# FMC_connector.net
KiCad netlist of a schematic drawn in Altium Designer
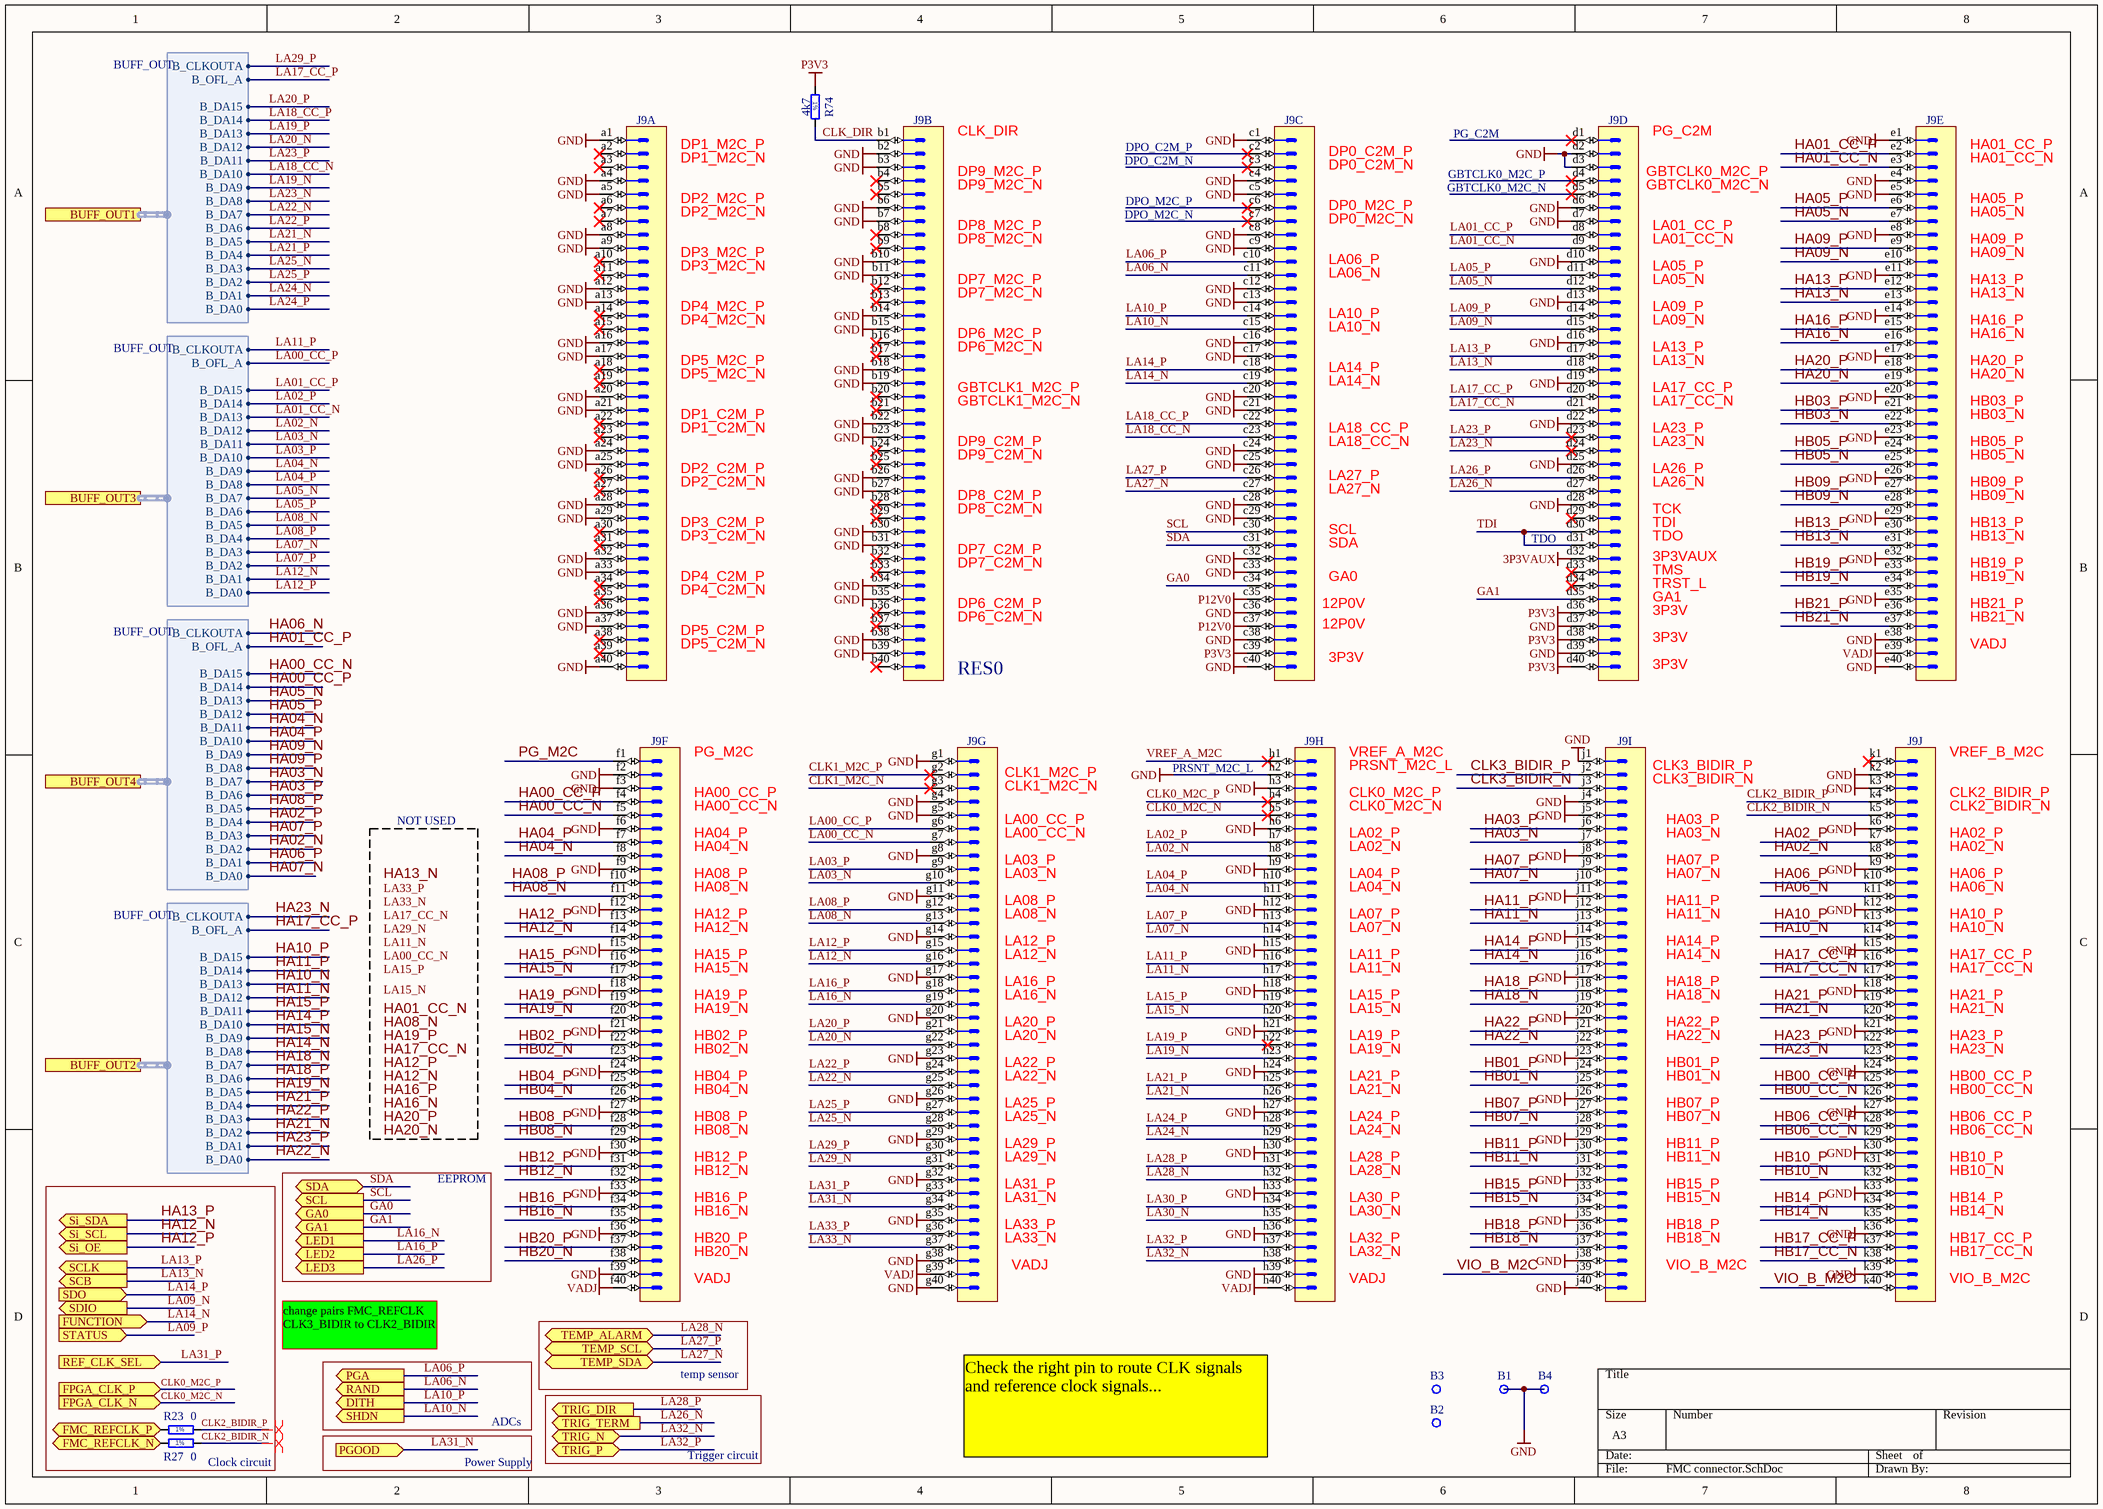
[diagram p0: FMC connector.SchDoc]

(export (version "E")
  (design (tool "Eeschema 10.0.6"))
  (components
    (comp (ref "B1")
      (value "Plated Hole")
      (footprint "MTG300_600")
      (description "Single Terminal Socket")
      (fields (field (name "PART NUMBER") "PLATED_HOLE3.0_PAD6.0") (field (name "AUTHOR") "CERN DEM JLC"))
      (libsource (lib "Eletro-mechanical") (part "Single Terminal Socket"))
    )
    (comp (ref "B2")
      (value "Plated Hole")
      (footprint "MTG300_600")
      (description "Single Terminal Socket")
      (fields (field (name "PART NUMBER") "PLATED_HOLE3.0_PAD6.0") (field (name "AUTHOR") "CERN DEM JLC"))
      (libsource (lib "Eletro-mechanical") (part "Single Terminal Socket"))
    )
    (comp (ref "B3")
      (value "Plated Hole")
      (footprint "MTG300_600")
      (description "Single Terminal Socket")
      (fields (field (name "PART NUMBER") "PLATED_HOLE3.0_PAD6.0") (field (name "AUTHOR") "CERN DEM JLC"))
      (libsource (lib "Eletro-mechanical") (part "Single Terminal Socket"))
    )
    (comp (ref "B4")
      (value "Plated Hole")
      (footprint "MTG300_600")
      (description "Single Terminal Socket")
      (fields (field (name "PART NUMBER") "PLATED_HOLE3.0_PAD6.0") (field (name "AUTHOR") "CERN DEM JLC"))
      (libsource (lib "Eletro-mechanical") (part "Single Terminal Socket"))
    )
    (comp (ref "J9")
      (value "VITA 57")
      (footprint "SAMTEC_ASP-134488-01")
      (description "Connector VITA 57, 400 Male contacts in 10 row abcdefghj")
      (fields
        (field (name "PART NUMBER") "SAMTEC_ASP-134488-01")
        (field (name "MANUFACTURER") "SAMTEC")
        (field (name "AUTHOR") "CERN DEM JLC")
      )
      (libsource (lib "Connectors") (part "Connector VITA 57 400 Male (abcdefghjk)"))
    )
    (comp (ref "R23")
      (value "0")
      (footprint "RESC1005X40N")
      (description "Resistor - 1%")
      (fields
        (field (name "PART NUMBER") "R0402_0R_JUMPER")
        (field (name "MANUFACTURER") "GENERIC")
        (field (name "AUTHOR") "CERN DEM JLC")
      )
      (libsource (lib "Resistors") (part "Resistor - 1%"))
    )
    (comp (ref "R27")
      (value "0")
      (footprint "RESC1005X40N")
      (description "Resistor - 1%")
      (fields
        (field (name "PART NUMBER") "R0402_0R_JUMPER")
        (field (name "MANUFACTURER") "GENERIC")
        (field (name "AUTHOR") "CERN DEM JLC")
      )
      (libsource (lib "Resistors") (part "Resistor - 1%"))
    )
    (comp (ref "R74")
      (value "4k7")
      (footprint "RESC1608X55N")
      (description "Resistor - 1%")
      (fields
        (field (name "PART NUMBER") "R0603_4K7_1%_0.1W_100PPM")
        (field (name "POWER") "0.1W")
        (field (name "AUTHOR") "CERN DEM JLC")
      )
      (libsource (lib "Resistors") (part "Resistor - 1%"))
    )
  )
  (nets
    (net (code "2") (name "/CLK0_M2C_N") (class "Default")
      (node (ref "J9") (pin "h5") (pinfunction "h5_h5") (pintype "bidirectional+no_connect"))
    )
    (net (code "3") (name "/CLK0_M2C_P") (class "Default")
      (node (ref "J9") (pin "h4") (pinfunction "h4_h4") (pintype "bidirectional+no_connect"))
    )
    (net (code "4") (name "/CLK1_M2C_N") (class "Default")
      (node (ref "J9") (pin "g3") (pinfunction "g3_g3") (pintype "bidirectional+no_connect"))
    )
    (net (code "5") (name "/CLK1_M2C_P") (class "Default")
      (node (ref "J9") (pin "g2") (pinfunction "g2_g2") (pintype "bidirectional+no_connect"))
    )
    (net (code "6") (name "/CLK2_BIDIR_N") (class "Default")
      (node (ref "J9") (pin "k5") (pinfunction "k5_k5") (pintype "bidirectional"))
      (node (ref "R27") (pin "2") (pinfunction "2_2") (pintype "passive"))
    )
    (net (code "7") (name "/CLK2_BIDIR_P") (class "Default")
      (node (ref "J9") (pin "k4") (pinfunction "k4_k4") (pintype "bidirectional"))
      (node (ref "R23") (pin "2") (pinfunction "2_2") (pintype "passive"))
    )
    (net (code "8") (name "/CLK3_BIDIR_N") (class "Default")
      (node (ref "J9") (pin "j3") (pinfunction "j3_j3") (pintype "bidirectional"))
    )
    (net (code "9") (name "/CLK3_BIDIR_P") (class "Default")
      (node (ref "J9") (pin "j2") (pinfunction "j2_j2") (pintype "bidirectional"))
    )
    (net (code "10") (name "/CLK_DIR") (class "Default")
      (node (ref "J9") (pin "b1") (pinfunction "b1_b1") (pintype "bidirectional"))
      (node (ref "R74") (pin "2") (pinfunction "2_2") (pintype "passive"))
    )
    (net (code "11") (name "/FMC_REFCLK_N") (class "Default")
      (node (ref "R27") (pin "1") (pinfunction "1_1") (pintype "passive"))
    )
    (net (code "12") (name "/FMC_REFCLK_P") (class "Default")
      (node (ref "R23") (pin "1") (pinfunction "1_1") (pintype "passive"))
    )
    (net (code "13") (name "/GA0") (class "Default")
      (node (ref "J9") (pin "c34") (pinfunction "c34_c34") (pintype "bidirectional"))
    )
    (net (code "14") (name "/GA1") (class "Default")
      (node (ref "J9") (pin "d35") (pinfunction "d35_d35") (pintype "bidirectional"))
    )
    (net (code "15") (name "/HA00_CC_N") (class "Default")
      (node (ref "J9") (pin "f5") (pinfunction "f5_f5") (pintype "bidirectional"))
    )
    (net (code "16") (name "/HA00_CC_P") (class "Default")
      (node (ref "J9") (pin "f4") (pinfunction "f4_f4") (pintype "bidirectional"))
    )
    (net (code "17") (name "/HA01_CC_N") (class "Default")
      (node (ref "J9") (pin "e3") (pinfunction "e3_e3") (pintype "bidirectional"))
    )
    (net (code "18") (name "/HA01_CC_P") (class "Default")
      (node (ref "J9") (pin "e2") (pinfunction "e2_e2") (pintype "bidirectional"))
    )
    (net (code "19") (name "/HA02_N") (class "Default")
      (node (ref "J9") (pin "k8") (pinfunction "k8_k8") (pintype "bidirectional"))
    )
    (net (code "20") (name "/HA02_P") (class "Default")
      (node (ref "J9") (pin "k7") (pinfunction "k7_k7") (pintype "bidirectional"))
    )
    (net (code "21") (name "/HA03_N") (class "Default")
      (node (ref "J9") (pin "j7") (pinfunction "j7_j7") (pintype "bidirectional"))
    )
    (net (code "22") (name "/HA03_P") (class "Default")
      (node (ref "J9") (pin "j6") (pinfunction "j6_j6") (pintype "bidirectional"))
    )
    (net (code "23") (name "/HA04_N") (class "Default")
      (node (ref "J9") (pin "f8") (pinfunction "f8_f8") (pintype "bidirectional"))
    )
    (net (code "24") (name "/HA04_P") (class "Default")
      (node (ref "J9") (pin "f7") (pinfunction "f7_f7") (pintype "bidirectional"))
    )
    (net (code "25") (name "/HA05_N") (class "Default")
      (node (ref "J9") (pin "e7") (pinfunction "e7_e7") (pintype "bidirectional"))
    )
    (net (code "26") (name "/HA05_P") (class "Default")
      (node (ref "J9") (pin "e6") (pinfunction "e6_e6") (pintype "bidirectional"))
    )
    (net (code "27") (name "/HA06_N") (class "Default")
      (node (ref "J9") (pin "k11") (pinfunction "k11_k11") (pintype "bidirectional"))
    )
    (net (code "28") (name "/HA06_P") (class "Default")
      (node (ref "J9") (pin "k10") (pinfunction "k10_k10") (pintype "bidirectional"))
    )
    (net (code "29") (name "/HA07_N") (class "Default")
      (node (ref "J9") (pin "j10") (pinfunction "j10_j10") (pintype "bidirectional"))
    )
    (net (code "30") (name "/HA07_P") (class "Default")
      (node (ref "J9") (pin "j9") (pinfunction "j9_j9") (pintype "bidirectional"))
    )
    (net (code "31") (name "/HA08_N") (class "Default")
      (node (ref "J9") (pin "f11") (pinfunction "f11_f11") (pintype "bidirectional"))
    )
    (net (code "32") (name "/HA08_P") (class "Default")
      (node (ref "J9") (pin "f10") (pinfunction "f10_f10") (pintype "bidirectional"))
    )
    (net (code "33") (name "/HA09_N") (class "Default")
      (node (ref "J9") (pin "e10") (pinfunction "e10_e10") (pintype "bidirectional"))
    )
    (net (code "34") (name "/HA09_P") (class "Default")
      (node (ref "J9") (pin "e9") (pinfunction "e9_e9") (pintype "bidirectional"))
    )
    (net (code "35") (name "/HA10_N") (class "Default")
      (node (ref "J9") (pin "k14") (pinfunction "k14_k14") (pintype "bidirectional"))
    )
    (net (code "36") (name "/HA10_P") (class "Default")
      (node (ref "J9") (pin "k13") (pinfunction "k13_k13") (pintype "bidirectional"))
    )
    (net (code "37") (name "/HA11_N") (class "Default")
      (node (ref "J9") (pin "j13") (pinfunction "j13_j13") (pintype "bidirectional"))
    )
    (net (code "38") (name "/HA11_P") (class "Default")
      (node (ref "J9") (pin "j12") (pinfunction "j12_j12") (pintype "bidirectional"))
    )
    (net (code "39") (name "/HA12_N") (class "Default")
      (node (ref "J9") (pin "f14") (pinfunction "f14_f14") (pintype "bidirectional"))
    )
    (net (code "40") (name "/HA12_P") (class "Default")
      (node (ref "J9") (pin "f13") (pinfunction "f13_f13") (pintype "bidirectional"))
    )
    (net (code "41") (name "/HA13_N") (class "Default")
      (node (ref "J9") (pin "e13") (pinfunction "e13_e13") (pintype "bidirectional"))
    )
    (net (code "42") (name "/HA13_P") (class "Default")
      (node (ref "J9") (pin "e12") (pinfunction "e12_e12") (pintype "bidirectional"))
    )
    (net (code "43") (name "/HA14_N") (class "Default")
      (node (ref "J9") (pin "j16") (pinfunction "j16_j16") (pintype "bidirectional"))
    )
    (net (code "44") (name "/HA14_P") (class "Default")
      (node (ref "J9") (pin "j15") (pinfunction "j15_j15") (pintype "bidirectional"))
    )
    (net (code "45") (name "/HA15_N") (class "Default")
      (node (ref "J9") (pin "f17") (pinfunction "f17_f17") (pintype "bidirectional"))
    )
    (net (code "46") (name "/HA15_P") (class "Default")
      (node (ref "J9") (pin "f16") (pinfunction "f16_f16") (pintype "bidirectional"))
    )
    (net (code "47") (name "/HA16_N") (class "Default")
      (node (ref "J9") (pin "e16") (pinfunction "e16_e16") (pintype "bidirectional"))
    )
    (net (code "48") (name "/HA16_P") (class "Default")
      (node (ref "J9") (pin "e15") (pinfunction "e15_e15") (pintype "bidirectional"))
    )
    (net (code "49") (name "/HA17_CC_N") (class "Default")
      (node (ref "J9") (pin "k17") (pinfunction "k17_k17") (pintype "bidirectional"))
    )
    (net (code "50") (name "/HA17_CC_P") (class "Default")
      (node (ref "J9") (pin "k16") (pinfunction "k16_k16") (pintype "bidirectional"))
    )
    (net (code "51") (name "/HA18_N") (class "Default")
      (node (ref "J9") (pin "j19") (pinfunction "j19_j19") (pintype "bidirectional"))
    )
    (net (code "52") (name "/HA18_P") (class "Default")
      (node (ref "J9") (pin "j18") (pinfunction "j18_j18") (pintype "bidirectional"))
    )
    (net (code "53") (name "/HA19_N") (class "Default")
      (node (ref "J9") (pin "f20") (pinfunction "f20_f20") (pintype "bidirectional"))
    )
    (net (code "54") (name "/HA19_P") (class "Default")
      (node (ref "J9") (pin "f19") (pinfunction "f19_f19") (pintype "bidirectional"))
    )
    (net (code "55") (name "/HA20_N") (class "Default")
      (node (ref "J9") (pin "e19") (pinfunction "e19_e19") (pintype "bidirectional"))
    )
    (net (code "56") (name "/HA20_P") (class "Default")
      (node (ref "J9") (pin "e18") (pinfunction "e18_e18") (pintype "bidirectional"))
    )
    (net (code "57") (name "/HA21_N") (class "Default")
      (node (ref "J9") (pin "k20") (pinfunction "k20_k20") (pintype "bidirectional"))
    )
    (net (code "58") (name "/HA21_P") (class "Default")
      (node (ref "J9") (pin "k19") (pinfunction "k19_k19") (pintype "bidirectional"))
    )
    (net (code "59") (name "/HA22_N") (class "Default")
      (node (ref "J9") (pin "j22") (pinfunction "j22_j22") (pintype "bidirectional"))
    )
    (net (code "60") (name "/HA22_P") (class "Default")
      (node (ref "J9") (pin "j21") (pinfunction "j21_j21") (pintype "bidirectional"))
    )
    (net (code "61") (name "/HA23_N") (class "Default")
      (node (ref "J9") (pin "k23") (pinfunction "k23_k23") (pintype "bidirectional"))
    )
    (net (code "62") (name "/HA23_P") (class "Default")
      (node (ref "J9") (pin "k22") (pinfunction "k22_k22") (pintype "bidirectional"))
    )
    (net (code "63") (name "/HB00_CC_N") (class "Default")
      (node (ref "J9") (pin "k26") (pinfunction "k26_k26") (pintype "bidirectional"))
    )
    (net (code "64") (name "/HB00_CC_P") (class "Default")
      (node (ref "J9") (pin "k25") (pinfunction "k25_k25") (pintype "bidirectional"))
    )
    (net (code "65") (name "/HB01_N") (class "Default")
      (node (ref "J9") (pin "j25") (pinfunction "j25_j25") (pintype "bidirectional"))
    )
    (net (code "66") (name "/HB01_P") (class "Default")
      (node (ref "J9") (pin "j24") (pinfunction "j24_j24") (pintype "bidirectional"))
    )
    (net (code "67") (name "/HB02_N") (class "Default")
      (node (ref "J9") (pin "f23") (pinfunction "f23_f23") (pintype "bidirectional"))
    )
    (net (code "68") (name "/HB02_P") (class "Default")
      (node (ref "J9") (pin "f22") (pinfunction "f22_f22") (pintype "bidirectional"))
    )
    (net (code "69") (name "/HB03_N") (class "Default")
      (node (ref "J9") (pin "e22") (pinfunction "e22_e22") (pintype "bidirectional"))
    )
    (net (code "70") (name "/HB03_P") (class "Default")
      (node (ref "J9") (pin "e21") (pinfunction "e21_e21") (pintype "bidirectional"))
    )
    (net (code "71") (name "/HB04_N") (class "Default")
      (node (ref "J9") (pin "f26") (pinfunction "f26_f26") (pintype "bidirectional"))
    )
    (net (code "72") (name "/HB04_P") (class "Default")
      (node (ref "J9") (pin "f25") (pinfunction "f25_f25") (pintype "bidirectional"))
    )
    (net (code "73") (name "/HB05_N") (class "Default")
      (node (ref "J9") (pin "e25") (pinfunction "e25_e25") (pintype "bidirectional"))
    )
    (net (code "74") (name "/HB05_P") (class "Default")
      (node (ref "J9") (pin "e24") (pinfunction "e24_e24") (pintype "bidirectional"))
    )
    (net (code "75") (name "/HB06_CC_N") (class "Default")
      (node (ref "J9") (pin "k29") (pinfunction "k29_k29") (pintype "bidirectional"))
    )
    (net (code "76") (name "/HB06_CC_P") (class "Default")
      (node (ref "J9") (pin "k28") (pinfunction "k28_k28") (pintype "bidirectional"))
    )
    (net (code "77") (name "/HB07_N") (class "Default")
      (node (ref "J9") (pin "j28") (pinfunction "j28_j28") (pintype "bidirectional"))
    )
    (net (code "78") (name "/HB07_P") (class "Default")
      (node (ref "J9") (pin "j27") (pinfunction "j27_j27") (pintype "bidirectional"))
    )
    (net (code "79") (name "/HB08_N") (class "Default")
      (node (ref "J9") (pin "f29") (pinfunction "f29_f29") (pintype "bidirectional"))
    )
    (net (code "80") (name "/HB08_P") (class "Default")
      (node (ref "J9") (pin "f28") (pinfunction "f28_f28") (pintype "bidirectional"))
    )
    (net (code "81") (name "/HB09_N") (class "Default")
      (node (ref "J9") (pin "e28") (pinfunction "e28_e28") (pintype "bidirectional"))
    )
    (net (code "82") (name "/HB09_P") (class "Default")
      (node (ref "J9") (pin "e27") (pinfunction "e27_e27") (pintype "bidirectional"))
    )
    (net (code "83") (name "/HB10_N") (class "Default")
      (node (ref "J9") (pin "k32") (pinfunction "k32_k32") (pintype "bidirectional"))
    )
    (net (code "84") (name "/HB10_P") (class "Default")
      (node (ref "J9") (pin "k31") (pinfunction "k31_k31") (pintype "bidirectional"))
    )
    (net (code "85") (name "/HB11_N") (class "Default")
      (node (ref "J9") (pin "j31") (pinfunction "j31_j31") (pintype "bidirectional"))
    )
    (net (code "86") (name "/HB11_P") (class "Default")
      (node (ref "J9") (pin "j30") (pinfunction "j30_j30") (pintype "bidirectional"))
    )
    (net (code "87") (name "/HB12_N") (class "Default")
      (node (ref "J9") (pin "f32") (pinfunction "f32_f32") (pintype "bidirectional"))
    )
    (net (code "88") (name "/HB12_P") (class "Default")
      (node (ref "J9") (pin "f31") (pinfunction "f31_f31") (pintype "bidirectional"))
    )
    (net (code "89") (name "/HB13_N") (class "Default")
      (node (ref "J9") (pin "e31") (pinfunction "e31_e31") (pintype "bidirectional"))
    )
    (net (code "90") (name "/HB13_P") (class "Default")
      (node (ref "J9") (pin "e30") (pinfunction "e30_e30") (pintype "bidirectional"))
    )
    (net (code "91") (name "/HB14_N") (class "Default")
      (node (ref "J9") (pin "k35") (pinfunction "k35_k35") (pintype "bidirectional"))
    )
    (net (code "92") (name "/HB14_P") (class "Default")
      (node (ref "J9") (pin "k34") (pinfunction "k34_k34") (pintype "bidirectional"))
    )
    (net (code "93") (name "/HB15_N") (class "Default")
      (node (ref "J9") (pin "j34") (pinfunction "j34_j34") (pintype "bidirectional"))
    )
    (net (code "94") (name "/HB15_P") (class "Default")
      (node (ref "J9") (pin "j33") (pinfunction "j33_j33") (pintype "bidirectional"))
    )
    (net (code "95") (name "/HB16_N") (class "Default")
      (node (ref "J9") (pin "f35") (pinfunction "f35_f35") (pintype "bidirectional"))
    )
    (net (code "96") (name "/HB16_P") (class "Default")
      (node (ref "J9") (pin "f34") (pinfunction "f34_f34") (pintype "bidirectional"))
    )
    (net (code "97") (name "/HB17_CC_N") (class "Default")
      (node (ref "J9") (pin "k38") (pinfunction "k38_k38") (pintype "bidirectional"))
    )
    (net (code "98") (name "/HB17_CC_P") (class "Default")
      (node (ref "J9") (pin "k37") (pinfunction "k37_k37") (pintype "bidirectional"))
    )
    (net (code "99") (name "/HB18_N") (class "Default")
      (node (ref "J9") (pin "j37") (pinfunction "j37_j37") (pintype "bidirectional"))
    )
    (net (code "100") (name "/HB18_P") (class "Default")
      (node (ref "J9") (pin "j36") (pinfunction "j36_j36") (pintype "bidirectional"))
    )
    (net (code "101") (name "/HB19_N") (class "Default")
      (node (ref "J9") (pin "e34") (pinfunction "e34_e34") (pintype "bidirectional"))
    )
    (net (code "102") (name "/HB19_P") (class "Default")
      (node (ref "J9") (pin "e33") (pinfunction "e33_e33") (pintype "bidirectional"))
    )
    (net (code "103") (name "/HB20_N") (class "Default")
      (node (ref "J9") (pin "f38") (pinfunction "f38_f38") (pintype "bidirectional"))
    )
    (net (code "104") (name "/HB20_P") (class "Default")
      (node (ref "J9") (pin "f37") (pinfunction "f37_f37") (pintype "bidirectional"))
    )
    (net (code "105") (name "/HB21_N") (class "Default")
      (node (ref "J9") (pin "e37") (pinfunction "e37_e37") (pintype "bidirectional"))
    )
    (net (code "106") (name "/HB21_P") (class "Default")
      (node (ref "J9") (pin "e36") (pinfunction "e36_e36") (pintype "bidirectional"))
    )
    (net (code "107") (name "/LA00_CC_N") (class "Default")
      (node (ref "J9") (pin "g7") (pinfunction "g7_g7") (pintype "bidirectional"))
    )
    (net (code "108") (name "/LA00_CC_P") (class "Default")
      (node (ref "J9") (pin "g6") (pinfunction "g6_g6") (pintype "bidirectional"))
    )
    (net (code "109") (name "/LA01_CC_N") (class "Default")
      (node (ref "J9") (pin "d9") (pinfunction "d9_d9") (pintype "bidirectional"))
    )
    (net (code "110") (name "/LA01_CC_P") (class "Default")
      (node (ref "J9") (pin "d8") (pinfunction "d8_d8") (pintype "bidirectional"))
    )
    (net (code "111") (name "/LA02_N") (class "Default")
      (node (ref "J9") (pin "h8") (pinfunction "h8_h8") (pintype "bidirectional"))
    )
    (net (code "112") (name "/LA02_P") (class "Default")
      (node (ref "J9") (pin "h7") (pinfunction "h7_h7") (pintype "bidirectional"))
    )
    (net (code "113") (name "/LA03_N") (class "Default")
      (node (ref "J9") (pin "g10") (pinfunction "g10_g10") (pintype "bidirectional"))
    )
    (net (code "114") (name "/LA03_P") (class "Default")
      (node (ref "J9") (pin "g9") (pinfunction "g9_g9") (pintype "bidirectional"))
    )
    (net (code "115") (name "/LA04_N") (class "Default")
      (node (ref "J9") (pin "h11") (pinfunction "h11_h11") (pintype "bidirectional"))
    )
    (net (code "116") (name "/LA04_P") (class "Default")
      (node (ref "J9") (pin "h10") (pinfunction "h10_h10") (pintype "bidirectional"))
    )
    (net (code "117") (name "/LA05_N") (class "Default")
      (node (ref "J9") (pin "d12") (pinfunction "d12_d12") (pintype "bidirectional"))
    )
    (net (code "118") (name "/LA05_P") (class "Default")
      (node (ref "J9") (pin "d11") (pinfunction "d11_d11") (pintype "bidirectional"))
    )
    (net (code "119") (name "/LA06_N") (class "Default")
      (node (ref "J9") (pin "c11") (pinfunction "c11_c11") (pintype "bidirectional"))
    )
    (net (code "120") (name "/LA06_P") (class "Default")
      (node (ref "J9") (pin "c10") (pinfunction "c10_c10") (pintype "bidirectional"))
    )
    (net (code "121") (name "/LA07_N") (class "Default")
      (node (ref "J9") (pin "h14") (pinfunction "h14_h14") (pintype "bidirectional"))
    )
    (net (code "122") (name "/LA07_P") (class "Default")
      (node (ref "J9") (pin "h13") (pinfunction "h13_h13") (pintype "bidirectional"))
    )
    (net (code "123") (name "/LA08_N") (class "Default")
      (node (ref "J9") (pin "g13") (pinfunction "g13_g13") (pintype "bidirectional"))
    )
    (net (code "124") (name "/LA08_P") (class "Default")
      (node (ref "J9") (pin "g12") (pinfunction "g12_g12") (pintype "bidirectional"))
    )
    (net (code "125") (name "/LA09_N") (class "Default")
      (node (ref "J9") (pin "d15") (pinfunction "d15_d15") (pintype "bidirectional"))
    )
    (net (code "126") (name "/LA09_P") (class "Default")
      (node (ref "J9") (pin "d14") (pinfunction "d14_d14") (pintype "bidirectional"))
    )
    (net (code "127") (name "/LA10_N") (class "Default")
      (node (ref "J9") (pin "c15") (pinfunction "c15_c15") (pintype "bidirectional"))
    )
    (net (code "128") (name "/LA10_P") (class "Default")
      (node (ref "J9") (pin "c14") (pinfunction "c14_c14") (pintype "bidirectional"))
    )
    (net (code "129") (name "/LA11_N") (class "Default")
      (node (ref "J9") (pin "h17") (pinfunction "h17_h17") (pintype "bidirectional"))
    )
    (net (code "130") (name "/LA11_P") (class "Default")
      (node (ref "J9") (pin "h16") (pinfunction "h16_h16") (pintype "bidirectional"))
    )
    (net (code "131") (name "/LA12_N") (class "Default")
      (node (ref "J9") (pin "g16") (pinfunction "g16_g16") (pintype "bidirectional"))
    )
    (net (code "132") (name "/LA12_P") (class "Default")
      (node (ref "J9") (pin "g15") (pinfunction "g15_g15") (pintype "bidirectional"))
    )
    (net (code "133") (name "/LA13_N") (class "Default")
      (node (ref "J9") (pin "d18") (pinfunction "d18_d18") (pintype "bidirectional"))
    )
    (net (code "134") (name "/LA13_P") (class "Default")
      (node (ref "J9") (pin "d17") (pinfunction "d17_d17") (pintype "bidirectional"))
    )
    (net (code "135") (name "/LA14_N") (class "Default")
      (node (ref "J9") (pin "c19") (pinfunction "c19_c19") (pintype "bidirectional"))
    )
    (net (code "136") (name "/LA14_P") (class "Default")
      (node (ref "J9") (pin "c18") (pinfunction "c18_c18") (pintype "bidirectional"))
    )
    (net (code "137") (name "/LA15_N") (class "Default")
      (node (ref "J9") (pin "h20") (pinfunction "h20_h20") (pintype "bidirectional"))
    )
    (net (code "138") (name "/LA15_P") (class "Default")
      (node (ref "J9") (pin "h19") (pinfunction "h19_h19") (pintype "bidirectional"))
    )
    (net (code "139") (name "/LA16_N") (class "Default")
      (node (ref "J9") (pin "g19") (pinfunction "g19_g19") (pintype "bidirectional"))
    )
    (net (code "140") (name "/LA16_P") (class "Default")
      (node (ref "J9") (pin "g18") (pinfunction "g18_g18") (pintype "bidirectional"))
    )
    (net (code "141") (name "/LA17_CC_N") (class "Default")
      (node (ref "J9") (pin "d21") (pinfunction "d21_d21") (pintype "bidirectional"))
    )
    (net (code "142") (name "/LA17_CC_P") (class "Default")
      (node (ref "J9") (pin "d20") (pinfunction "d20_d20") (pintype "bidirectional"))
    )
    (net (code "143") (name "/LA18_CC_N") (class "Default")
      (node (ref "J9") (pin "c23") (pinfunction "c23_c23") (pintype "bidirectional"))
    )
    (net (code "144") (name "/LA18_CC_P") (class "Default")
      (node (ref "J9") (pin "c22") (pinfunction "c22_c22") (pintype "bidirectional"))
    )
    (net (code "145") (name "/LA19_N") (class "Default")
      (node (ref "J9") (pin "h23") (pinfunction "h23_h23") (pintype "bidirectional"))
    )
    (net (code "146") (name "/LA19_P") (class "Default")
      (node (ref "J9") (pin "h22") (pinfunction "h22_h22") (pintype "bidirectional+no_connect"))
    )
    (net (code "147") (name "/LA20_N") (class "Default")
      (node (ref "J9") (pin "g22") (pinfunction "g22_g22") (pintype "bidirectional"))
    )
    (net (code "148") (name "/LA20_P") (class "Default")
      (node (ref "J9") (pin "g21") (pinfunction "g21_g21") (pintype "bidirectional"))
    )
    (net (code "149") (name "/LA21_N") (class "Default")
      (node (ref "J9") (pin "h26") (pinfunction "h26_h26") (pintype "bidirectional"))
    )
    (net (code "150") (name "/LA21_P") (class "Default")
      (node (ref "J9") (pin "h25") (pinfunction "h25_h25") (pintype "bidirectional"))
    )
    (net (code "151") (name "/LA22_N") (class "Default")
      (node (ref "J9") (pin "g25") (pinfunction "g25_g25") (pintype "bidirectional"))
    )
    (net (code "152") (name "/LA22_P") (class "Default")
      (node (ref "J9") (pin "g24") (pinfunction "g24_g24") (pintype "bidirectional"))
    )
    (net (code "153") (name "/LA23_N") (class "Default")
      (node (ref "J9") (pin "d24") (pinfunction "d24_d24") (pintype "bidirectional+no_connect"))
    )
    (net (code "154") (name "/LA23_P") (class "Default")
      (node (ref "J9") (pin "d23") (pinfunction "d23_d23") (pintype "bidirectional+no_connect"))
    )
    (net (code "155") (name "/LA24_N") (class "Default")
      (node (ref "J9") (pin "h29") (pinfunction "h29_h29") (pintype "bidirectional"))
    )
    (net (code "156") (name "/LA24_P") (class "Default")
      (node (ref "J9") (pin "h28") (pinfunction "h28_h28") (pintype "bidirectional"))
    )
    (net (code "157") (name "/LA25_N") (class "Default")
      (node (ref "J9") (pin "g28") (pinfunction "g28_g28") (pintype "bidirectional"))
    )
    (net (code "158") (name "/LA25_P") (class "Default")
      (node (ref "J9") (pin "g27") (pinfunction "g27_g27") (pintype "bidirectional"))
    )
    (net (code "159") (name "/LA26_N") (class "Default")
      (node (ref "J9") (pin "d27") (pinfunction "d27_d27") (pintype "bidirectional"))
    )
    (net (code "160") (name "/LA26_P") (class "Default")
      (node (ref "J9") (pin "d26") (pinfunction "d26_d26") (pintype "bidirectional"))
    )
    (net (code "161") (name "/LA27_N") (class "Default")
      (node (ref "J9") (pin "c27") (pinfunction "c27_c27") (pintype "bidirectional"))
    )
    (net (code "162") (name "/LA27_P") (class "Default")
      (node (ref "J9") (pin "c26") (pinfunction "c26_c26") (pintype "bidirectional"))
    )
    (net (code "163") (name "/LA28_N") (class "Default")
      (node (ref "J9") (pin "h32") (pinfunction "h32_h32") (pintype "bidirectional"))
    )
    (net (code "164") (name "/LA28_P") (class "Default")
      (node (ref "J9") (pin "h31") (pinfunction "h31_h31") (pintype "bidirectional"))
    )
    (net (code "165") (name "/LA29_N") (class "Default")
      (node (ref "J9") (pin "g31") (pinfunction "g31_g31") (pintype "bidirectional"))
    )
    (net (code "166") (name "/LA29_P") (class "Default")
      (node (ref "J9") (pin "g30") (pinfunction "g30_g30") (pintype "bidirectional"))
    )
    (net (code "167") (name "/LA30_N") (class "Default")
      (node (ref "J9") (pin "h35") (pinfunction "h35_h35") (pintype "bidirectional"))
    )
    (net (code "168") (name "/LA30_P") (class "Default")
      (node (ref "J9") (pin "h34") (pinfunction "h34_h34") (pintype "bidirectional"))
    )
    (net (code "169") (name "/LA31_N") (class "Default")
      (node (ref "J9") (pin "g34") (pinfunction "g34_g34") (pintype "bidirectional"))
    )
    (net (code "170") (name "/LA31_P") (class "Default")
      (node (ref "J9") (pin "g33") (pinfunction "g33_g33") (pintype "bidirectional"))
    )
    (net (code "171") (name "/LA32_N") (class "Default")
      (node (ref "J9") (pin "h38") (pinfunction "h38_h38") (pintype "bidirectional"))
    )
    (net (code "172") (name "/LA32_P") (class "Default")
      (node (ref "J9") (pin "h37") (pinfunction "h37_h37") (pintype "bidirectional"))
    )
    (net (code "173") (name "/LA33_N") (class "Default")
      (node (ref "J9") (pin "g37") (pinfunction "g37_g37") (pintype "bidirectional"))
    )
    (net (code "174") (name "/LA33_P") (class "Default")
      (node (ref "J9") (pin "g36") (pinfunction "g36_g36") (pintype "bidirectional"))
    )
    (net (code "175") (name "/PG_M2C") (class "Default")
      (node (ref "J9") (pin "f1") (pinfunction "f1_f1") (pintype "bidirectional"))
    )
    (net (code "176") (name "/SCL") (class "Default")
      (node (ref "J9") (pin "c30") (pinfunction "c30_c30") (pintype "bidirectional"))
    )
    (net (code "177") (name "/SDA") (class "Default")
      (node (ref "J9") (pin "c31") (pinfunction "c31_c31") (pintype "bidirectional"))
    )
    (net (code "178") (name "/TDI") (class "Default")
      (node (ref "J9") (pin "d30") (pinfunction "d30_d30") (pintype "bidirectional"))
      (node (ref "J9") (pin "d31") (pinfunction "d31_d31") (pintype "bidirectional"))
    )
    (net (code "179") (name "/VIO_B_M2C") (class "Default")
      (node (ref "J9") (pin "j39") (pinfunction "j39_j39") (pintype "bidirectional"))
      (node (ref "J9") (pin "k40") (pinfunction "k40_k40") (pintype "bidirectional"))
    )
    (net (code "180") (name "/VREF_A_M2C") (class "Default")
      (node (ref "J9") (pin "h1") (pinfunction "h1_h1") (pintype "bidirectional+no_connect"))
    )
    (net (code "182") (name "3P3VAUX") (class "Default")
      (node (ref "J9") (pin "d32") (pinfunction "d32_d32") (pintype "bidirectional"))
    )
    (net (code "183") (name "GND") (class "Default")
      (node (ref "B1") (pin "1") (pinfunction "1_1") (pintype "bidirectional"))
      (node (ref "B4") (pin "1") (pinfunction "1_1") (pintype "bidirectional"))
      (node (ref "J9") (pin "a1") (pinfunction "a1_a1") (pintype "bidirectional"))
      (node (ref "J9") (pin "a12") (pinfunction "a12_a12") (pintype "bidirectional"))
      (node (ref "J9") (pin "a13") (pinfunction "a13_a13") (pintype "bidirectional"))
      (node (ref "J9") (pin "a16") (pinfunction "a16_a16") (pintype "bidirectional"))
      (node (ref "J9") (pin "a17") (pinfunction "a17_a17") (pintype "bidirectional"))
      (node (ref "J9") (pin "a20") (pinfunction "a20_a20") (pintype "bidirectional"))
      (node (ref "J9") (pin "a21") (pinfunction "a21_a21") (pintype "bidirectional"))
      (node (ref "J9") (pin "a24") (pinfunction "a24_a24") (pintype "bidirectional"))
      (node (ref "J9") (pin "a25") (pinfunction "a25_a25") (pintype "bidirectional"))
      (node (ref "J9") (pin "a28") (pinfunction "a28_a28") (pintype "bidirectional"))
      (node (ref "J9") (pin "a29") (pinfunction "a29_a29") (pintype "bidirectional"))
      (node (ref "J9") (pin "a32") (pinfunction "a32_a32") (pintype "bidirectional"))
      (node (ref "J9") (pin "a33") (pinfunction "a33_a33") (pintype "bidirectional"))
      (node (ref "J9") (pin "a36") (pinfunction "a36_a36") (pintype "bidirectional"))
      (node (ref "J9") (pin "a37") (pinfunction "a37_a37") (pintype "bidirectional"))
      (node (ref "J9") (pin "a4") (pinfunction "a4_a4") (pintype "bidirectional"))
      (node (ref "J9") (pin "a40") (pinfunction "a40_a40") (pintype "bidirectional"))
      (node (ref "J9") (pin "a5") (pinfunction "a5_a5") (pintype "bidirectional"))
      (node (ref "J9") (pin "a8") (pinfunction "a8_a8") (pintype "bidirectional"))
      (node (ref "J9") (pin "a9") (pinfunction "a9_a9") (pintype "bidirectional"))
      (node (ref "J9") (pin "b10") (pinfunction "b10_b10") (pintype "bidirectional"))
      (node (ref "J9") (pin "b11") (pinfunction "b11_b11") (pintype "bidirectional"))
      (node (ref "J9") (pin "b14") (pinfunction "b14_b14") (pintype "bidirectional"))
      (node (ref "J9") (pin "b15") (pinfunction "b15_b15") (pintype "bidirectional"))
      (node (ref "J9") (pin "b18") (pinfunction "b18_b18") (pintype "bidirectional"))
      (node (ref "J9") (pin "b19") (pinfunction "b19_b19") (pintype "bidirectional"))
      (node (ref "J9") (pin "b2") (pinfunction "b2_b2") (pintype "bidirectional"))
      (node (ref "J9") (pin "b22") (pinfunction "b22_b22") (pintype "bidirectional"))
      (node (ref "J9") (pin "b23") (pinfunction "b23_b23") (pintype "bidirectional"))
      (node (ref "J9") (pin "b26") (pinfunction "b26_b26") (pintype "bidirectional"))
      (node (ref "J9") (pin "b27") (pinfunction "b27_b27") (pintype "bidirectional"))
      (node (ref "J9") (pin "b3") (pinfunction "b3_b3") (pintype "bidirectional"))
      (node (ref "J9") (pin "b30") (pinfunction "b30_b30") (pintype "bidirectional"))
      (node (ref "J9") (pin "b31") (pinfunction "b31_b31") (pintype "bidirectional"))
      (node (ref "J9") (pin "b34") (pinfunction "b34_b34") (pintype "bidirectional"))
      (node (ref "J9") (pin "b35") (pinfunction "b35_b35") (pintype "bidirectional"))
      (node (ref "J9") (pin "b38") (pinfunction "b38_b38") (pintype "bidirectional"))
      (node (ref "J9") (pin "b39") (pinfunction "b39_b39") (pintype "bidirectional"))
      (node (ref "J9") (pin "b6") (pinfunction "b6_b6") (pintype "bidirectional"))
      (node (ref "J9") (pin "b7") (pinfunction "b7_b7") (pintype "bidirectional"))
      (node (ref "J9") (pin "c1") (pinfunction "c1_c1") (pintype "bidirectional"))
      (node (ref "J9") (pin "c12") (pinfunction "c12_c12") (pintype "bidirectional"))
      (node (ref "J9") (pin "c13") (pinfunction "c13_c13") (pintype "bidirectional"))
      (node (ref "J9") (pin "c16") (pinfunction "c16_c16") (pintype "bidirectional"))
      (node (ref "J9") (pin "c17") (pinfunction "c17_c17") (pintype "bidirectional"))
      (node (ref "J9") (pin "c20") (pinfunction "c20_c20") (pintype "bidirectional"))
      (node (ref "J9") (pin "c21") (pinfunction "c21_c21") (pintype "bidirectional"))
      (node (ref "J9") (pin "c24") (pinfunction "c24_c24") (pintype "bidirectional"))
      (node (ref "J9") (pin "c25") (pinfunction "c25_c25") (pintype "bidirectional"))
      (node (ref "J9") (pin "c28") (pinfunction "c28_c28") (pintype "bidirectional"))
      (node (ref "J9") (pin "c29") (pinfunction "c29_c29") (pintype "bidirectional"))
      (node (ref "J9") (pin "c32") (pinfunction "c32_c32") (pintype "bidirectional"))
      (node (ref "J9") (pin "c33") (pinfunction "c33_c33") (pintype "bidirectional"))
      (node (ref "J9") (pin "c36") (pinfunction "c36_c36") (pintype "bidirectional"))
      (node (ref "J9") (pin "c38") (pinfunction "c38_c38") (pintype "bidirectional"))
      (node (ref "J9") (pin "c4") (pinfunction "c4_c4") (pintype "bidirectional"))
      (node (ref "J9") (pin "c40") (pinfunction "c40_c40") (pintype "bidirectional"))
      (node (ref "J9") (pin "c5") (pinfunction "c5_c5") (pintype "bidirectional"))
      (node (ref "J9") (pin "c8") (pinfunction "c8_c8") (pintype "bidirectional"))
      (node (ref "J9") (pin "c9") (pinfunction "c9_c9") (pintype "bidirectional"))
      (node (ref "J9") (pin "d10") (pinfunction "d10_d10") (pintype "bidirectional"))
      (node (ref "J9") (pin "d13") (pinfunction "d13_d13") (pintype "bidirectional"))
      (node (ref "J9") (pin "d16") (pinfunction "d16_d16") (pintype "bidirectional"))
      (node (ref "J9") (pin "d19") (pinfunction "d19_d19") (pintype "bidirectional"))
      (node (ref "J9") (pin "d2") (pinfunction "d2_d2") (pintype "bidirectional"))
      (node (ref "J9") (pin "d22") (pinfunction "d22_d22") (pintype "bidirectional"))
      (node (ref "J9") (pin "d25") (pinfunction "d25_d25") (pintype "bidirectional"))
      (node (ref "J9") (pin "d28") (pinfunction "d28_d28") (pintype "bidirectional"))
      (node (ref "J9") (pin "d3") (pinfunction "d3_d3") (pintype "bidirectional"))
      (node (ref "J9") (pin "d37") (pinfunction "d37_d37") (pintype "bidirectional"))
      (node (ref "J9") (pin "d39") (pinfunction "d39_d39") (pintype "bidirectional"))
      (node (ref "J9") (pin "d6") (pinfunction "d6_d6") (pintype "bidirectional"))
      (node (ref "J9") (pin "d7") (pinfunction "d7_d7") (pintype "bidirectional"))
      (node (ref "J9") (pin "e1") (pinfunction "e1_e1") (pintype "bidirectional"))
      (node (ref "J9") (pin "e11") (pinfunction "e11_e11") (pintype "bidirectional"))
      (node (ref "J9") (pin "e14") (pinfunction "e14_e14") (pintype "bidirectional"))
      (node (ref "J9") (pin "e17") (pinfunction "e17_e17") (pintype "bidirectional"))
      (node (ref "J9") (pin "e20") (pinfunction "e20_e20") (pintype "bidirectional"))
      (node (ref "J9") (pin "e23") (pinfunction "e23_e23") (pintype "bidirectional"))
      (node (ref "J9") (pin "e26") (pinfunction "e26_e26") (pintype "bidirectional"))
      (node (ref "J9") (pin "e29") (pinfunction "e29_e29") (pintype "bidirectional"))
      (node (ref "J9") (pin "e32") (pinfunction "e32_e32") (pintype "bidirectional"))
      (node (ref "J9") (pin "e35") (pinfunction "e35_e35") (pintype "bidirectional"))
      (node (ref "J9") (pin "e38") (pinfunction "e38_e38") (pintype "bidirectional"))
      (node (ref "J9") (pin "e4") (pinfunction "e4_e4") (pintype "bidirectional"))
      (node (ref "J9") (pin "e40") (pinfunction "e40_e40") (pintype "bidirectional"))
      (node (ref "J9") (pin "e5") (pinfunction "e5_e5") (pintype "bidirectional"))
      (node (ref "J9") (pin "e8") (pinfunction "e8_e8") (pintype "bidirectional"))
      (node (ref "J9") (pin "f12") (pinfunction "f12_f12") (pintype "bidirectional"))
      (node (ref "J9") (pin "f15") (pinfunction "f15_f15") (pintype "bidirectional"))
      (node (ref "J9") (pin "f18") (pinfunction "f18_f18") (pintype "bidirectional"))
      (node (ref "J9") (pin "f2") (pinfunction "f2_f2") (pintype "bidirectional"))
      (node (ref "J9") (pin "f21") (pinfunction "f21_f21") (pintype "bidirectional"))
      (node (ref "J9") (pin "f24") (pinfunction "f24_f24") (pintype "bidirectional"))
      (node (ref "J9") (pin "f27") (pinfunction "f27_f27") (pintype "bidirectional"))
      (node (ref "J9") (pin "f3") (pinfunction "f3_f3") (pintype "bidirectional"))
      (node (ref "J9") (pin "f30") (pinfunction "f30_f30") (pintype "bidirectional"))
      (node (ref "J9") (pin "f33") (pinfunction "f33_f33") (pintype "bidirectional"))
      (node (ref "J9") (pin "f36") (pinfunction "f36_f36") (pintype "bidirectional"))
      (node (ref "J9") (pin "f39") (pinfunction "f39_f39") (pintype "bidirectional"))
      (node (ref "J9") (pin "f6") (pinfunction "f6_f6") (pintype "bidirectional"))
      (node (ref "J9") (pin "f9") (pinfunction "f9_f9") (pintype "bidirectional"))
      (node (ref "J9") (pin "g1") (pinfunction "g1_g1") (pintype "bidirectional"))
      (node (ref "J9") (pin "g11") (pinfunction "g11_g11") (pintype "bidirectional"))
      (node (ref "J9") (pin "g14") (pinfunction "g14_g14") (pintype "bidirectional"))
      (node (ref "J9") (pin "g17") (pinfunction "g17_g17") (pintype "bidirectional"))
      (node (ref "J9") (pin "g20") (pinfunction "g20_g20") (pintype "bidirectional"))
      (node (ref "J9") (pin "g23") (pinfunction "g23_g23") (pintype "bidirectional"))
      (node (ref "J9") (pin "g26") (pinfunction "g26_g26") (pintype "bidirectional"))
      (node (ref "J9") (pin "g29") (pinfunction "g29_g29") (pintype "bidirectional"))
      (node (ref "J9") (pin "g32") (pinfunction "g32_g32") (pintype "bidirectional"))
      (node (ref "J9") (pin "g35") (pinfunction "g35_g35") (pintype "bidirectional"))
      (node (ref "J9") (pin "g38") (pinfunction "g38_g38") (pintype "bidirectional"))
      (node (ref "J9") (pin "g4") (pinfunction "g4_g4") (pintype "bidirectional"))
      (node (ref "J9") (pin "g40") (pinfunction "g40_g40") (pintype "bidirectional"))
      (node (ref "J9") (pin "g5") (pinfunction "g5_g5") (pintype "bidirectional"))
      (node (ref "J9") (pin "g8") (pinfunction "g8_g8") (pintype "bidirectional"))
      (node (ref "J9") (pin "h12") (pinfunction "h12_h12") (pintype "bidirectional"))
      (node (ref "J9") (pin "h15") (pinfunction "h15_h15") (pintype "bidirectional"))
      (node (ref "J9") (pin "h18") (pinfunction "h18_h18") (pintype "bidirectional"))
      (node (ref "J9") (pin "h2") (pinfunction "h2_h2") (pintype "bidirectional"))
      (node (ref "J9") (pin "h21") (pinfunction "h21_h21") (pintype "bidirectional"))
      (node (ref "J9") (pin "h24") (pinfunction "h24_h24") (pintype "bidirectional"))
      (node (ref "J9") (pin "h27") (pinfunction "h27_h27") (pintype "bidirectional"))
      (node (ref "J9") (pin "h3") (pinfunction "h3_h3") (pintype "bidirectional"))
      (node (ref "J9") (pin "h30") (pinfunction "h30_h30") (pintype "bidirectional"))
      (node (ref "J9") (pin "h33") (pinfunction "h33_h33") (pintype "bidirectional"))
      (node (ref "J9") (pin "h36") (pinfunction "h36_h36") (pintype "bidirectional"))
      (node (ref "J9") (pin "h39") (pinfunction "h39_h39") (pintype "bidirectional"))
      (node (ref "J9") (pin "h6") (pinfunction "h6_h6") (pintype "bidirectional"))
      (node (ref "J9") (pin "h9") (pinfunction "h9_h9") (pintype "bidirectional"))
      (node (ref "J9") (pin "j1") (pinfunction "j1_j1") (pintype "bidirectional"))
      (node (ref "J9") (pin "j11") (pinfunction "j11_j11") (pintype "bidirectional"))
      (node (ref "J9") (pin "j14") (pinfunction "j14_j14") (pintype "bidirectional"))
      (node (ref "J9") (pin "j17") (pinfunction "j17_j17") (pintype "bidirectional"))
      (node (ref "J9") (pin "j20") (pinfunction "j20_j20") (pintype "bidirectional"))
      (node (ref "J9") (pin "j23") (pinfunction "j23_j23") (pintype "bidirectional"))
      (node (ref "J9") (pin "j26") (pinfunction "j26_j26") (pintype "bidirectional"))
      (node (ref "J9") (pin "j29") (pinfunction "j29_j29") (pintype "bidirectional"))
      (node (ref "J9") (pin "j32") (pinfunction "j32_j32") (pintype "bidirectional"))
      (node (ref "J9") (pin "j35") (pinfunction "j35_j35") (pintype "bidirectional"))
      (node (ref "J9") (pin "j38") (pinfunction "j38_j38") (pintype "bidirectional"))
      (node (ref "J9") (pin "j4") (pinfunction "j4_j4") (pintype "bidirectional"))
      (node (ref "J9") (pin "j40") (pinfunction "j40_j40") (pintype "bidirectional"))
      (node (ref "J9") (pin "j5") (pinfunction "j5_j5") (pintype "bidirectional"))
      (node (ref "J9") (pin "j8") (pinfunction "j8_j8") (pintype "bidirectional"))
      (node (ref "J9") (pin "k12") (pinfunction "k12_k12") (pintype "bidirectional"))
      (node (ref "J9") (pin "k15") (pinfunction "k15_k15") (pintype "bidirectional"))
      (node (ref "J9") (pin "k18") (pinfunction "k18_k18") (pintype "bidirectional"))
      (node (ref "J9") (pin "k2") (pinfunction "k2_k2") (pintype "bidirectional"))
      (node (ref "J9") (pin "k21") (pinfunction "k21_k21") (pintype "bidirectional"))
      (node (ref "J9") (pin "k24") (pinfunction "k24_k24") (pintype "bidirectional"))
      (node (ref "J9") (pin "k27") (pinfunction "k27_k27") (pintype "bidirectional"))
      (node (ref "J9") (pin "k3") (pinfunction "k3_k3") (pintype "bidirectional"))
      (node (ref "J9") (pin "k30") (pinfunction "k30_k30") (pintype "bidirectional"))
      (node (ref "J9") (pin "k33") (pinfunction "k33_k33") (pintype "bidirectional"))
      (node (ref "J9") (pin "k36") (pinfunction "k36_k36") (pintype "bidirectional"))
      (node (ref "J9") (pin "k39") (pinfunction "k39_k39") (pintype "bidirectional"))
      (node (ref "J9") (pin "k6") (pinfunction "k6_k6") (pintype "bidirectional"))
      (node (ref "J9") (pin "k9") (pinfunction "k9_k9") (pintype "bidirectional"))
    )
    (net (code "184") (name "P3V3") (class "Default")
      (node (ref "J9") (pin "c39") (pinfunction "c39_c39") (pintype "bidirectional"))
      (node (ref "J9") (pin "d36") (pinfunction "d36_d36") (pintype "bidirectional"))
      (node (ref "J9") (pin "d38") (pinfunction "d38_d38") (pintype "bidirectional"))
      (node (ref "J9") (pin "d40") (pinfunction "d40_d40") (pintype "bidirectional"))
      (node (ref "R74") (pin "1") (pinfunction "1_1") (pintype "passive"))
    )
    (net (code "185") (name "P12V0") (class "Default")
      (node (ref "J9") (pin "c35") (pinfunction "c35_c35") (pintype "bidirectional"))
      (node (ref "J9") (pin "c37") (pinfunction "c37_c37") (pintype "bidirectional"))
    )
    (net (code "186") (name "VADJ") (class "Default")
      (node (ref "J9") (pin "e39") (pinfunction "e39_e39") (pintype "bidirectional"))
      (node (ref "J9") (pin "f40") (pinfunction "f40_f40") (pintype "bidirectional"))
      (node (ref "J9") (pin "g39") (pinfunction "g39_g39") (pintype "bidirectional"))
      (node (ref "J9") (pin "h40") (pinfunction "h40_h40") (pintype "bidirectional"))
    )
    (net (code "187") (name "unconnected-(B2-Pad1)") (class "Default")
      (node (ref "B2") (pin "1") (pinfunction "1_1") (pintype "bidirectional"))
    )
    (net (code "188") (name "unconnected-(B3-Pad1)") (class "Default")
      (node (ref "B3") (pin "1") (pinfunction "1_1") (pintype "bidirectional"))
    )
    (net (code "189") (name "unconnected-(J9-Pada2)") (class "Default")
      (node (ref "J9") (pin "a2") (pinfunction "a2_a2") (pintype "bidirectional+no_connect"))
    )
    (net (code "190") (name "unconnected-(J9-Pada3)") (class "Default")
      (node (ref "J9") (pin "a3") (pinfunction "a3_a3") (pintype "bidirectional+no_connect"))
    )
    (net (code "191") (name "unconnected-(J9-Pada6)") (class "Default")
      (node (ref "J9") (pin "a6") (pinfunction "a6_a6") (pintype "bidirectional+no_connect"))
    )
    (net (code "192") (name "unconnected-(J9-Pada7)") (class "Default")
      (node (ref "J9") (pin "a7") (pinfunction "a7_a7") (pintype "bidirectional+no_connect"))
    )
    (net (code "193") (name "unconnected-(J9-Pada10)") (class "Default")
      (node (ref "J9") (pin "a10") (pinfunction "a10_a10") (pintype "bidirectional+no_connect"))
    )
    (net (code "194") (name "unconnected-(J9-Pada11)") (class "Default")
      (node (ref "J9") (pin "a11") (pinfunction "a11_a11") (pintype "bidirectional+no_connect"))
    )
    (net (code "195") (name "unconnected-(J9-Pada14)") (class "Default")
      (node (ref "J9") (pin "a14") (pinfunction "a14_a14") (pintype "bidirectional+no_connect"))
    )
    (net (code "196") (name "unconnected-(J9-Pada15)") (class "Default")
      (node (ref "J9") (pin "a15") (pinfunction "a15_a15") (pintype "bidirectional+no_connect"))
    )
    (net (code "197") (name "unconnected-(J9-Pada18)") (class "Default")
      (node (ref "J9") (pin "a18") (pinfunction "a18_a18") (pintype "bidirectional+no_connect"))
    )
    (net (code "198") (name "unconnected-(J9-Pada19)") (class "Default")
      (node (ref "J9") (pin "a19") (pinfunction "a19_a19") (pintype "bidirectional+no_connect"))
    )
    (net (code "199") (name "unconnected-(J9-Pada22)") (class "Default")
      (node (ref "J9") (pin "a22") (pinfunction "a22_a22") (pintype "bidirectional+no_connect"))
    )
    (net (code "200") (name "unconnected-(J9-Pada23)") (class "Default")
      (node (ref "J9") (pin "a23") (pinfunction "a23_a23") (pintype "bidirectional+no_connect"))
    )
    (net (code "201") (name "unconnected-(J9-Pada26)") (class "Default")
      (node (ref "J9") (pin "a26") (pinfunction "a26_a26") (pintype "bidirectional+no_connect"))
    )
    (net (code "202") (name "unconnected-(J9-Pada27)") (class "Default")
      (node (ref "J9") (pin "a27") (pinfunction "a27_a27") (pintype "bidirectional+no_connect"))
    )
    (net (code "203") (name "unconnected-(J9-Pada30)") (class "Default")
      (node (ref "J9") (pin "a30") (pinfunction "a30_a30") (pintype "bidirectional+no_connect"))
    )
    (net (code "204") (name "unconnected-(J9-Pada31)") (class "Default")
      (node (ref "J9") (pin "a31") (pinfunction "a31_a31") (pintype "bidirectional+no_connect"))
    )
    (net (code "205") (name "unconnected-(J9-Pada34)") (class "Default")
      (node (ref "J9") (pin "a34") (pinfunction "a34_a34") (pintype "bidirectional+no_connect"))
    )
    (net (code "206") (name "unconnected-(J9-Pada35)") (class "Default")
      (node (ref "J9") (pin "a35") (pinfunction "a35_a35") (pintype "bidirectional+no_connect"))
    )
    (net (code "207") (name "unconnected-(J9-Pada38)") (class "Default")
      (node (ref "J9") (pin "a38") (pinfunction "a38_a38") (pintype "bidirectional+no_connect"))
    )
    (net (code "208") (name "unconnected-(J9-Pada39)") (class "Default")
      (node (ref "J9") (pin "a39") (pinfunction "a39_a39") (pintype "bidirectional+no_connect"))
    )
    (net (code "209") (name "unconnected-(J9-Padb4)") (class "Default")
      (node (ref "J9") (pin "b4") (pinfunction "b4_b4") (pintype "bidirectional+no_connect"))
    )
    (net (code "210") (name "unconnected-(J9-Padb5)") (class "Default")
      (node (ref "J9") (pin "b5") (pinfunction "b5_b5") (pintype "bidirectional+no_connect"))
    )
    (net (code "211") (name "unconnected-(J9-Padb8)") (class "Default")
      (node (ref "J9") (pin "b8") (pinfunction "b8_b8") (pintype "bidirectional+no_connect"))
    )
    (net (code "212") (name "unconnected-(J9-Padb9)") (class "Default")
      (node (ref "J9") (pin "b9") (pinfunction "b9_b9") (pintype "bidirectional+no_connect"))
    )
    (net (code "213") (name "unconnected-(J9-Padb12)") (class "Default")
      (node (ref "J9") (pin "b12") (pinfunction "b12_b12") (pintype "bidirectional+no_connect"))
    )
    (net (code "214") (name "unconnected-(J9-Padb13)") (class "Default")
      (node (ref "J9") (pin "b13") (pinfunction "b13_b13") (pintype "bidirectional+no_connect"))
    )
    (net (code "215") (name "unconnected-(J9-Padb16)") (class "Default")
      (node (ref "J9") (pin "b16") (pinfunction "b16_b16") (pintype "bidirectional+no_connect"))
    )
    (net (code "216") (name "unconnected-(J9-Padb17)") (class "Default")
      (node (ref "J9") (pin "b17") (pinfunction "b17_b17") (pintype "bidirectional+no_connect"))
    )
    (net (code "217") (name "unconnected-(J9-Padb20)") (class "Default")
      (node (ref "J9") (pin "b20") (pinfunction "b20_b20") (pintype "bidirectional+no_connect"))
    )
    (net (code "218") (name "unconnected-(J9-Padb21)") (class "Default")
      (node (ref "J9") (pin "b21") (pinfunction "b21_b21") (pintype "bidirectional+no_connect"))
    )
    (net (code "219") (name "unconnected-(J9-Padb24)") (class "Default")
      (node (ref "J9") (pin "b24") (pinfunction "b24_b24") (pintype "bidirectional+no_connect"))
    )
    (net (code "220") (name "unconnected-(J9-Padb25)") (class "Default")
      (node (ref "J9") (pin "b25") (pinfunction "b25_b25") (pintype "bidirectional+no_connect"))
    )
    (net (code "221") (name "unconnected-(J9-Padb28)") (class "Default")
      (node (ref "J9") (pin "b28") (pinfunction "b28_b28") (pintype "bidirectional+no_connect"))
    )
    (net (code "222") (name "unconnected-(J9-Padb29)") (class "Default")
      (node (ref "J9") (pin "b29") (pinfunction "b29_b29") (pintype "bidirectional+no_connect"))
    )
    (net (code "223") (name "unconnected-(J9-Padb32)") (class "Default")
      (node (ref "J9") (pin "b32") (pinfunction "b32_b32") (pintype "bidirectional+no_connect"))
    )
    (net (code "224") (name "unconnected-(J9-Padb33)") (class "Default")
      (node (ref "J9") (pin "b33") (pinfunction "b33_b33") (pintype "bidirectional+no_connect"))
    )
    (net (code "225") (name "unconnected-(J9-Padb36)") (class "Default")
      (node (ref "J9") (pin "b36") (pinfunction "b36_b36") (pintype "bidirectional+no_connect"))
    )
    (net (code "226") (name "unconnected-(J9-Padb37)") (class "Default")
      (node (ref "J9") (pin "b37") (pinfunction "b37_b37") (pintype "bidirectional+no_connect"))
    )
    (net (code "227") (name "unconnected-(J9-Padb40)") (class "Default")
      (node (ref "J9") (pin "b40") (pinfunction "b40_b40") (pintype "bidirectional+no_connect"))
    )
    (net (code "228") (name "unconnected-(J9-Padc2)") (class "Default")
      (node (ref "J9") (pin "c2") (pinfunction "c2_c2") (pintype "bidirectional+no_connect"))
    )
    (net (code "229") (name "unconnected-(J9-Padc3)") (class "Default")
      (node (ref "J9") (pin "c3") (pinfunction "c3_c3") (pintype "bidirectional+no_connect"))
    )
    (net (code "230") (name "unconnected-(J9-Padc6)") (class "Default")
      (node (ref "J9") (pin "c6") (pinfunction "c6_c6") (pintype "bidirectional+no_connect"))
    )
    (net (code "231") (name "unconnected-(J9-Padc7)") (class "Default")
      (node (ref "J9") (pin "c7") (pinfunction "c7_c7") (pintype "bidirectional+no_connect"))
    )
    (net (code "232") (name "unconnected-(J9-Padd1)") (class "Default")
      (node (ref "J9") (pin "d1") (pinfunction "d1_d1") (pintype "bidirectional+no_connect"))
    )
    (net (code "233") (name "unconnected-(J9-Padd4)") (class "Default")
      (node (ref "J9") (pin "d4") (pinfunction "d4_d4") (pintype "bidirectional+no_connect"))
    )
    (net (code "234") (name "unconnected-(J9-Padd5)") (class "Default")
      (node (ref "J9") (pin "d5") (pinfunction "d5_d5") (pintype "bidirectional+no_connect"))
    )
    (net (code "235") (name "unconnected-(J9-Padd29)") (class "Default")
      (node (ref "J9") (pin "d29") (pinfunction "d29_d29") (pintype "bidirectional+no_connect"))
    )
    (net (code "236") (name "unconnected-(J9-Padd33)") (class "Default")
      (node (ref "J9") (pin "d33") (pinfunction "d33_d33") (pintype "bidirectional+no_connect"))
    )
    (net (code "237") (name "unconnected-(J9-Padd34)") (class "Default")
      (node (ref "J9") (pin "d34") (pinfunction "d34_d34") (pintype "bidirectional+no_connect"))
    )
    (net (code "238") (name "unconnected-(J9-Padk1)") (class "Default")
      (node (ref "J9") (pin "k1") (pinfunction "k1_k1") (pintype "bidirectional+no_connect"))
    )
  )
)
